# Arduinomini.net
KiCad netlist of a schematic drawn in EAGLE
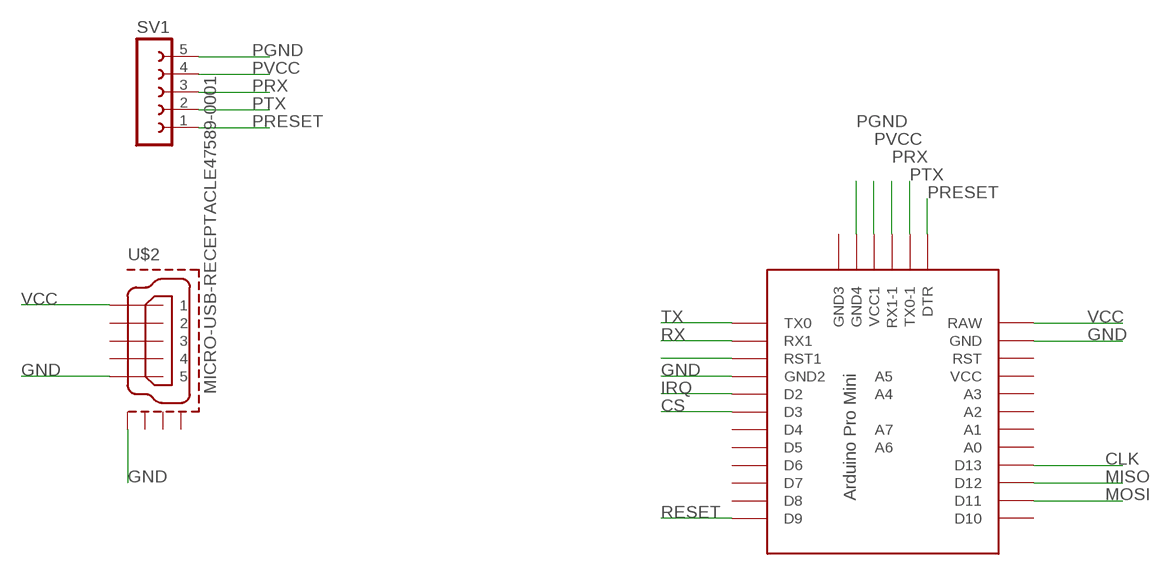
[diagram p0: schematic, sheet 1]

(export (version "E")
  (design (tool "Eeschema 10.0.6"))
  (components
    (comp (ref "SV1")
      (value "FE05-1")
      (footprint "eagle-import:FE05-1")
      (libsource (lib "eagle-import") (part "FE05-1"))
    )
    (comp (ref "U$1")
      (value "PRO-MINI-2")
      (footprint "eagle-import:PRO-MINI-2")
      (libsource (lib "eagle-import") (part "PRO-MINI-2"))
    )
    (comp (ref "U$2")
      (value "MICRO-USB-RECEPTACLE47589-0001")
      (footprint "eagle-import:47589-0001")
      (libsource (lib "eagle-import") (part "MICRO-USB-RECEPTACLE47589-0001"))
    )
  )
  (nets
    (net (code "1") (name "/CLK") (class "Default")
      (node (ref "U$1") (pin "D13") (pinfunction "D13_D13") (pintype "bidirectional"))
    )
    (net (code "2") (name "/CS") (class "Default")
      (node (ref "U$1") (pin "D3") (pinfunction "D3_D3") (pintype "bidirectional"))
    )
    (net (code "3") (name "/GND") (class "Default")
      (node (ref "U$1") (pin "GND") (pinfunction "GND_GND") (pintype "bidirectional"))
      (node (ref "U$1") (pin "GND1") (pinfunction "GND2_GND1") (pintype "bidirectional"))
      (node (ref "U$2") (pin "5") (pinfunction "5_5") (pintype "input"))
      (node (ref "U$2") (pin "CASING1") (pinfunction "GND1_CASING1") (pintype "bidirectional"))
    )
    (net (code "4") (name "/IRQ") (class "Default")
      (node (ref "U$1") (pin "D2") (pinfunction "D2_D2") (pintype "bidirectional"))
    )
    (net (code "5") (name "/MISO") (class "Default")
      (node (ref "U$1") (pin "D12") (pinfunction "D12_D12") (pintype "bidirectional"))
    )
    (net (code "6") (name "/MOSI") (class "Default")
      (node (ref "U$1") (pin "D11") (pinfunction "D11_D11") (pintype "bidirectional"))
    )
    (net (code "7") (name "/PGND") (class "Default")
      (node (ref "SV1") (pin "5") (pinfunction "5_5") (pintype "passive"))
      (node (ref "U$1") (pin "GND3") (pinfunction "GND4_GND3") (pintype "bidirectional"))
    )
    (net (code "8") (name "/PRESET") (class "Default")
      (node (ref "SV1") (pin "1") (pinfunction "1_1") (pintype "passive"))
      (node (ref "U$1") (pin "DTR") (pinfunction "DTR_DTR") (pintype "bidirectional"))
    )
    (net (code "9") (name "/PRX") (class "Default")
      (node (ref "SV1") (pin "3") (pinfunction "3_3") (pintype "passive"))
      (node (ref "U$1") (pin "RX1-1") (pinfunction "RX1-1_RX1-1") (pintype "bidirectional"))
    )
    (net (code "10") (name "/PTX") (class "Default")
      (node (ref "SV1") (pin "2") (pinfunction "2_2") (pintype "passive"))
      (node (ref "U$1") (pin "TX0-1") (pinfunction "TX0-1_TX0-1") (pintype "bidirectional"))
    )
    (net (code "11") (name "/PVCC") (class "Default")
      (node (ref "SV1") (pin "4") (pinfunction "4_4") (pintype "passive"))
      (node (ref "U$1") (pin "VCC1") (pinfunction "VCC1_VCC1") (pintype "bidirectional"))
    )
    (net (code "12") (name "/RESET") (class "Default")
      (node (ref "U$1") (pin "D9") (pinfunction "D9_D9") (pintype "bidirectional"))
    )
    (net (code "13") (name "/RX") (class "Default")
      (node (ref "U$1") (pin "RX1") (pinfunction "RX1_RX1") (pintype "bidirectional"))
    )
    (net (code "14") (name "/TX") (class "Default")
      (node (ref "U$1") (pin "TX0") (pinfunction "TX0_TX0") (pintype "bidirectional"))
    )
    (net (code "15") (name "/VCC") (class "Default")
      (node (ref "U$1") (pin "RAW") (pinfunction "RAW_RAW") (pintype "bidirectional"))
      (node (ref "U$2") (pin "1") (pinfunction "1_1") (pintype "input"))
    )
    (net (code "16") (name "unconnected-(U$1-GND3-PadGND2)") (class "Default")
      (node (ref "U$1") (pin "GND2") (pinfunction "GND3_GND2") (pintype "bidirectional"))
    )
    (net (code "17") (name "unconnected-(U$1-PadA0)") (class "Default")
      (node (ref "U$1") (pin "A0") (pinfunction "A0_A0") (pintype "bidirectional"))
    )
    (net (code "18") (name "unconnected-(U$1-PadA1)") (class "Default")
      (node (ref "U$1") (pin "A1") (pinfunction "A1_A1") (pintype "bidirectional"))
    )
    (net (code "19") (name "unconnected-(U$1-PadA2)") (class "Default")
      (node (ref "U$1") (pin "A2") (pinfunction "A2_A2") (pintype "bidirectional"))
    )
    (net (code "20") (name "unconnected-(U$1-PadA3)") (class "Default")
      (node (ref "U$1") (pin "A3") (pinfunction "A3_A3") (pintype "bidirectional"))
    )
    (net (code "21") (name "unconnected-(U$1-PadA4)") (class "Default")
      (node (ref "U$1") (pin "A4") (pinfunction "A4_A4") (pintype "bidirectional"))
    )
    (net (code "22") (name "unconnected-(U$1-PadA5)") (class "Default")
      (node (ref "U$1") (pin "A5") (pinfunction "A5_A5") (pintype "bidirectional"))
    )
    (net (code "23") (name "unconnected-(U$1-PadA6)") (class "Default")
      (node (ref "U$1") (pin "A6") (pinfunction "A6_A6") (pintype "bidirectional"))
    )
    (net (code "24") (name "unconnected-(U$1-PadA7)") (class "Default")
      (node (ref "U$1") (pin "A7") (pinfunction "A7_A7") (pintype "bidirectional"))
    )
    (net (code "25") (name "unconnected-(U$1-PadD4)") (class "Default")
      (node (ref "U$1") (pin "D4") (pinfunction "D4_D4") (pintype "bidirectional"))
    )
    (net (code "26") (name "unconnected-(U$1-PadD5)") (class "Default")
      (node (ref "U$1") (pin "D5") (pinfunction "D5_D5") (pintype "bidirectional"))
    )
    (net (code "27") (name "unconnected-(U$1-PadD6)") (class "Default")
      (node (ref "U$1") (pin "D6") (pinfunction "D6_D6") (pintype "bidirectional"))
    )
    (net (code "28") (name "unconnected-(U$1-PadD7)") (class "Default")
      (node (ref "U$1") (pin "D7") (pinfunction "D7_D7") (pintype "bidirectional"))
    )
    (net (code "29") (name "unconnected-(U$1-PadD8)") (class "Default")
      (node (ref "U$1") (pin "D8") (pinfunction "D8_D8") (pintype "bidirectional"))
    )
    (net (code "30") (name "unconnected-(U$1-PadD10)") (class "Default")
      (node (ref "U$1") (pin "D10") (pinfunction "D10_D10") (pintype "bidirectional"))
    )
    (net (code "31") (name "unconnected-(U$1-PadRST)") (class "Default")
      (node (ref "U$1") (pin "RST") (pinfunction "RST_RST") (pintype "bidirectional"))
    )
    (net (code "32") (name "unconnected-(U$1-PadRST1)") (class "Default")
      (node (ref "U$1") (pin "RST1") (pinfunction "RST1_RST1") (pintype "bidirectional"))
    )
    (net (code "33") (name "unconnected-(U$1-PadVCC)") (class "Default")
      (node (ref "U$1") (pin "VCC") (pinfunction "VCC_VCC") (pintype "bidirectional"))
    )
    (net (code "34") (name "unconnected-(U$2-GND2-PadCASING2)") (class "Default")
      (node (ref "U$2") (pin "CASING2") (pinfunction "GND2_CASING2") (pintype "bidirectional"))
    )
    (net (code "35") (name "unconnected-(U$2-GND3-PadCASING3)") (class "Default")
      (node (ref "U$2") (pin "CASING3") (pinfunction "GND3_CASING3") (pintype "bidirectional"))
    )
    (net (code "36") (name "unconnected-(U$2-GND4-PadCASING4)") (class "Default")
      (node (ref "U$2") (pin "CASING4") (pinfunction "GND4_CASING4") (pintype "bidirectional"))
    )
    (net (code "37") (name "unconnected-(U$2-Pad2)") (class "Default")
      (node (ref "U$2") (pin "2") (pinfunction "2_2") (pintype "input"))
    )
    (net (code "38") (name "unconnected-(U$2-Pad3)") (class "Default")
      (node (ref "U$2") (pin "3") (pinfunction "3_3") (pintype "input"))
    )
    (net (code "39") (name "unconnected-(U$2-Pad4)") (class "Default")
      (node (ref "U$2") (pin "4") (pinfunction "4_4") (pintype "input"))
    )
  )
)
